# robot_board.net
KiCad netlist of a schematic drawn in EAGLE
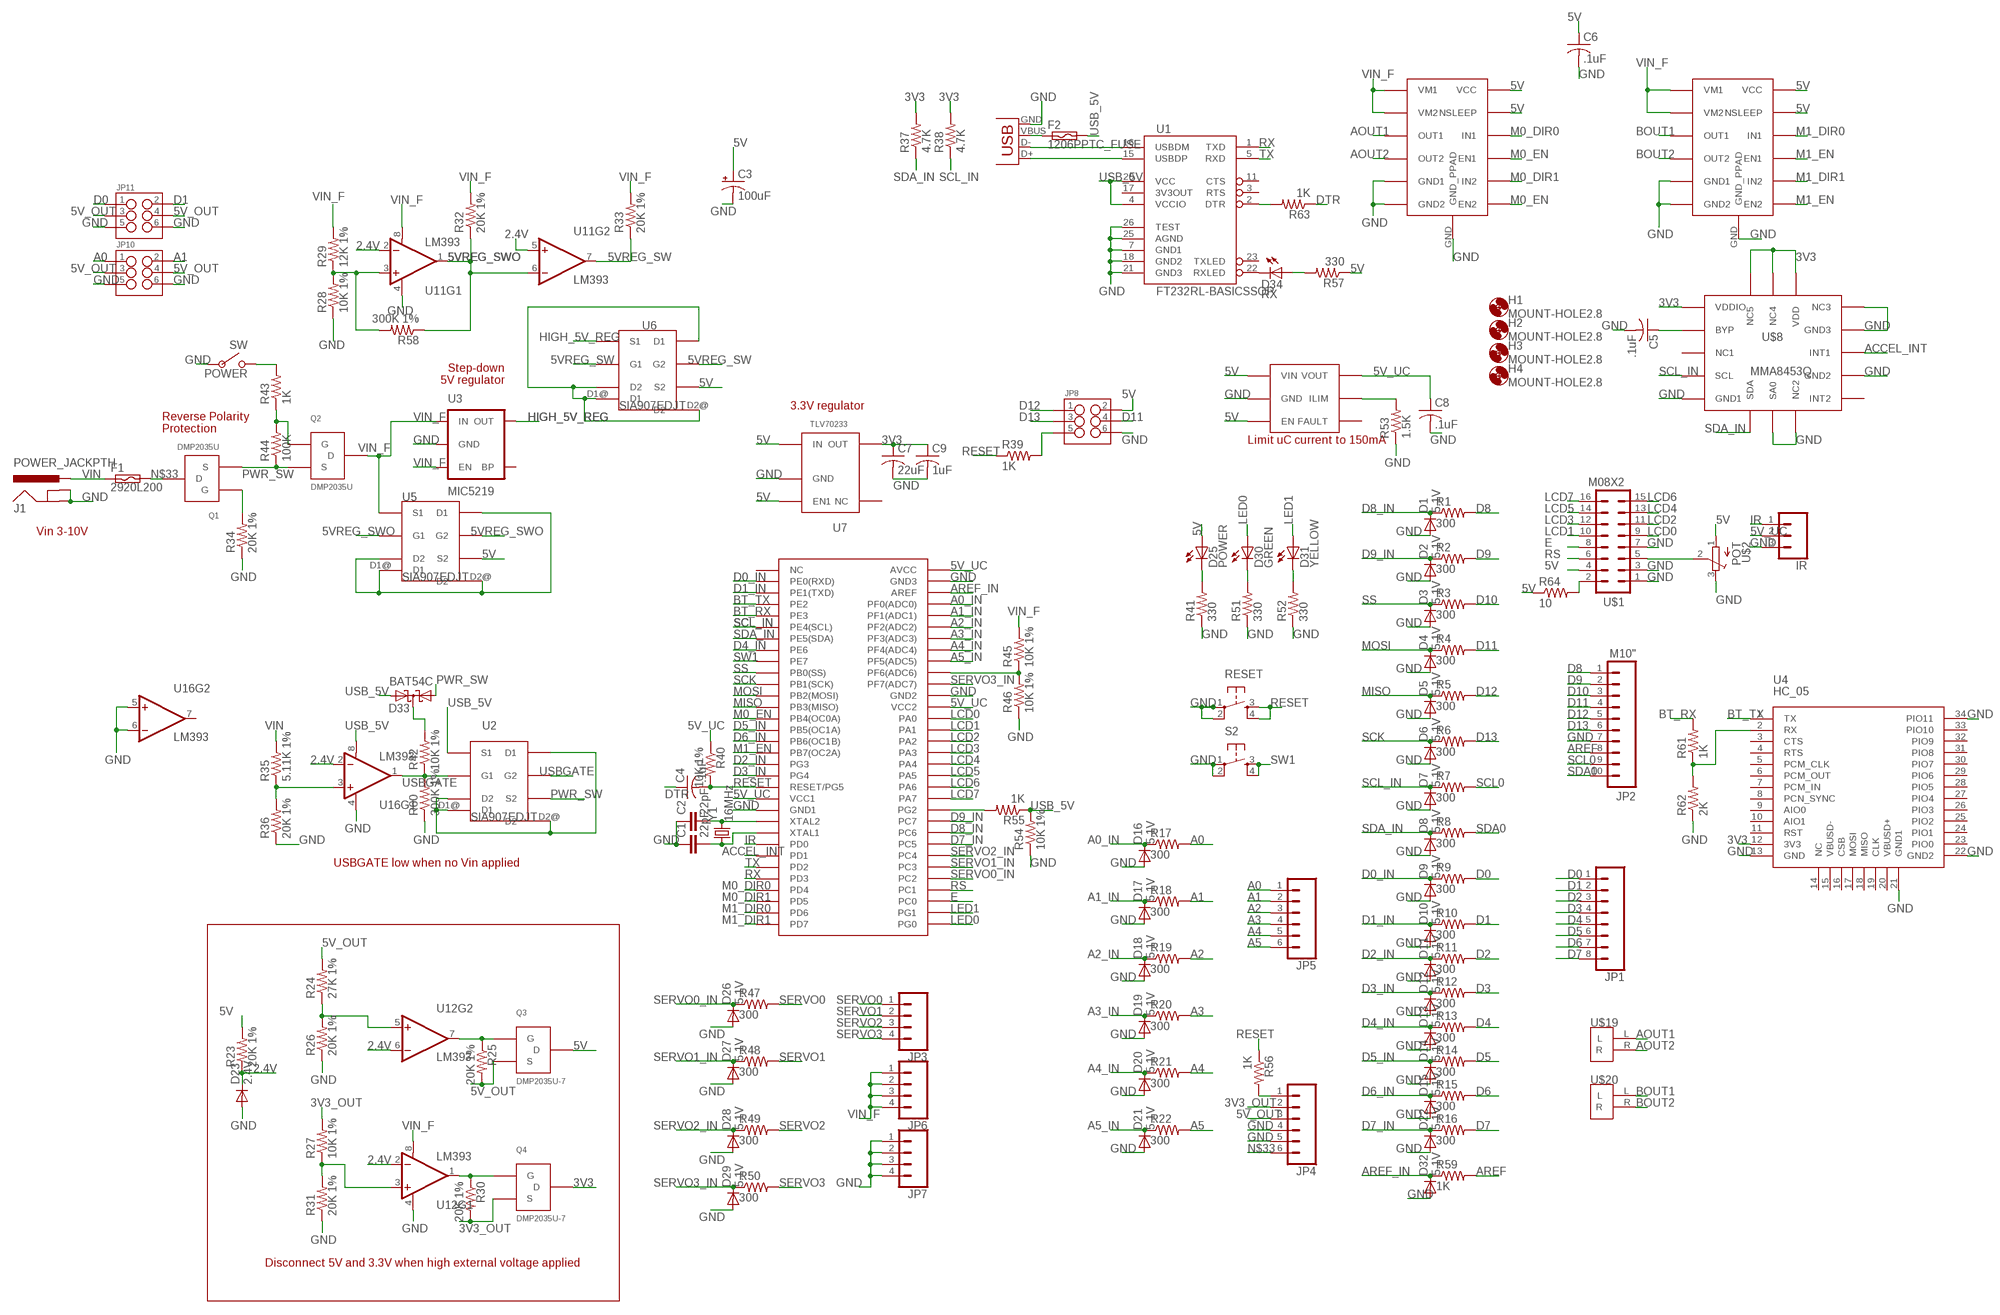
[diagram p0: schematic, sheet 1]

(export (version "E")
  (design (tool "Eeschema 10.0.6"))
  (components
    (comp (ref "C1")
      (value "22pF")
      (footprint "eagle-import:0805")
      (libsource (lib "eagle-import") (part "CAP0805"))
    )
    (comp (ref "C2")
      (value "22pF")
      (footprint "eagle-import:0805")
      (libsource (lib "eagle-import") (part "CAP0805"))
    )
    (comp (ref "C3")
      (value "100uF")
      (footprint "eagle-import:PANASONIC_D")
      (libsource (lib "eagle-import") (part "CAP_POLD"))
    )
    (comp (ref "C4")
      (value ".1uF")
      (footprint "eagle-import:C1206")
      (libsource (lib "eagle-import") (part "C-USC1206"))
    )
    (comp (ref "C5")
      (value ".1uF")
      (footprint "eagle-import:C1206")
      (libsource (lib "eagle-import") (part "C-USC1206"))
    )
    (comp (ref "C6")
      (value ".1uF")
      (footprint "eagle-import:C1206")
      (libsource (lib "eagle-import") (part "C-USC1206"))
    )
    (comp (ref "C7")
      (value "22uF")
      (footprint "eagle-import:C1206")
      (libsource (lib "eagle-import") (part "C-USC1206"))
    )
    (comp (ref "C8")
      (value ".1uF")
      (footprint "eagle-import:C1206")
      (libsource (lib "eagle-import") (part "C-USC1206"))
    )
    (comp (ref "C9")
      (value "1uF")
      (footprint "eagle-import:C1206")
      (libsource (lib "eagle-import") (part "C-USC1206"))
    )
    (comp (ref "D1")
      (value "5.1V")
      (footprint "eagle-import:SOT23-3")
      (libsource (lib "eagle-import") (part "DIODESOT23"))
    )
    (comp (ref "D2")
      (value "5.1V")
      (footprint "eagle-import:SOT23-3")
      (libsource (lib "eagle-import") (part "DIODESOT23"))
    )
    (comp (ref "D3")
      (value "5.1V")
      (footprint "eagle-import:SOT23-3")
      (libsource (lib "eagle-import") (part "DIODESOT23"))
    )
    (comp (ref "D4")
      (value "5.1V")
      (footprint "eagle-import:SOT23-3")
      (libsource (lib "eagle-import") (part "DIODESOT23"))
    )
    (comp (ref "D5")
      (value "5.1V")
      (footprint "eagle-import:SOT23-3")
      (libsource (lib "eagle-import") (part "DIODESOT23"))
    )
    (comp (ref "D6")
      (value "5.1V")
      (footprint "eagle-import:SOT23-3")
      (libsource (lib "eagle-import") (part "DIODESOT23"))
    )
    (comp (ref "D7")
      (value "5.1V")
      (footprint "eagle-import:SOT23-3")
      (libsource (lib "eagle-import") (part "DIODESOT23"))
    )
    (comp (ref "D8")
      (value "5.1V")
      (footprint "eagle-import:SOT23-3")
      (libsource (lib "eagle-import") (part "DIODESOT23"))
    )
    (comp (ref "D9")
      (value "5.1V")
      (footprint "eagle-import:SOT23-3")
      (libsource (lib "eagle-import") (part "DIODESOT23"))
    )
    (comp (ref "D10")
      (value "5.1V")
      (footprint "eagle-import:SOT23-3")
      (libsource (lib "eagle-import") (part "DIODESOT23"))
    )
    (comp (ref "D11")
      (value "5.1V")
      (footprint "eagle-import:SOT23-3")
      (libsource (lib "eagle-import") (part "DIODESOT23"))
    )
    (comp (ref "D12")
      (value "5.1V")
      (footprint "eagle-import:SOT23-3")
      (libsource (lib "eagle-import") (part "DIODESOT23"))
    )
    (comp (ref "D13")
      (value "5.1V")
      (footprint "eagle-import:SOT23-3")
      (libsource (lib "eagle-import") (part "DIODESOT23"))
    )
    (comp (ref "D14")
      (value "5.1V")
      (footprint "eagle-import:SOT23-3")
      (libsource (lib "eagle-import") (part "DIODESOT23"))
    )
    (comp (ref "D15")
      (value "5.1V")
      (footprint "eagle-import:SOT23-3")
      (libsource (lib "eagle-import") (part "DIODESOT23"))
    )
    (comp (ref "D16")
      (value "5.1V")
      (footprint "eagle-import:SOT23-3")
      (libsource (lib "eagle-import") (part "DIODESOT23"))
    )
    (comp (ref "D17")
      (value "5.1V")
      (footprint "eagle-import:SOT23-3")
      (libsource (lib "eagle-import") (part "DIODESOT23"))
    )
    (comp (ref "D18")
      (value "5.1V")
      (footprint "eagle-import:SOT23-3")
      (libsource (lib "eagle-import") (part "DIODESOT23"))
    )
    (comp (ref "D19")
      (value "5.1V")
      (footprint "eagle-import:SOT23-3")
      (libsource (lib "eagle-import") (part "DIODESOT23"))
    )
    (comp (ref "D20")
      (value "5.1V")
      (footprint "eagle-import:SOT23-3")
      (libsource (lib "eagle-import") (part "DIODESOT23"))
    )
    (comp (ref "D21")
      (value "5.1V")
      (footprint "eagle-import:SOT23-3")
      (libsource (lib "eagle-import") (part "DIODESOT23"))
    )
    (comp (ref "D22")
      (value "5.1V")
      (footprint "eagle-import:SOT23-3")
      (libsource (lib "eagle-import") (part "DIODESOT23"))
    )
    (comp (ref "D23")
      (value "2.4V")
      (footprint "eagle-import:SOT23-3")
      (libsource (lib "eagle-import") (part "DIODESOT23"))
    )
    (comp (ref "D25")
      (value "POWER")
      (footprint "eagle-import:LED-1206")
      (libsource (lib "eagle-import") (part "LED-GREENLILYPAD"))
    )
    (comp (ref "D26")
      (value "5.1V")
      (footprint "eagle-import:SOT23-3")
      (libsource (lib "eagle-import") (part "DIODESOT23"))
    )
    (comp (ref "D27")
      (value "5.1V")
      (footprint "eagle-import:SOT23-3")
      (libsource (lib "eagle-import") (part "DIODESOT23"))
    )
    (comp (ref "D28")
      (value "5.1V")
      (footprint "eagle-import:SOT23-3")
      (libsource (lib "eagle-import") (part "DIODESOT23"))
    )
    (comp (ref "D29")
      (value "5.1V")
      (footprint "eagle-import:SOT23-3")
      (libsource (lib "eagle-import") (part "DIODESOT23"))
    )
    (comp (ref "D30")
      (value "GREEN")
      (footprint "eagle-import:LED-1206")
      (libsource (lib "eagle-import") (part "LED-GREENLILYPAD"))
    )
    (comp (ref "D31")
      (value "YELLOW")
      (footprint "eagle-import:LED-1206")
      (libsource (lib "eagle-import") (part "LED-GREENLILYPAD"))
    )
    (comp (ref "D32")
      (value "5.1V")
      (footprint "eagle-import:SOT23-3")
      (libsource (lib "eagle-import") (part "DIODESOT23"))
    )
    (comp (ref "D33")
      (value "BAT54C")
      (footprint "eagle-import:SOT23")
      (libsource (lib "eagle-import") (part "BAT54C"))
    )
    (comp (ref "D34")
      (value "RX")
      (footprint "eagle-import:LED-1206")
      (libsource (lib "eagle-import") (part "LED-GREENLILYPAD"))
    )
    (comp (ref "F1")
      (value "2920L200")
      (footprint "eagle-import:SMD050F")
      (libsource (lib "eagle-import") (part "2920L200"))
    )
    (comp (ref "F2")
      (value "1206PPTC_FUSE")
      (footprint "eagle-import:R1206")
      (libsource (lib "eagle-import") (part "1206PPTC_FUSE"))
    )
    (comp (ref "H1")
      (value "MOUNT-HOLE2.8")
      (footprint "eagle-import:2,8")
      (libsource (lib "eagle-import") (part "MOUNT-HOLE2.8"))
    )
    (comp (ref "H2")
      (value "MOUNT-HOLE2.8")
      (footprint "eagle-import:2,8")
      (libsource (lib "eagle-import") (part "MOUNT-HOLE2.8"))
    )
    (comp (ref "H3")
      (value "MOUNT-HOLE2.8")
      (footprint "eagle-import:2,8")
      (libsource (lib "eagle-import") (part "MOUNT-HOLE2.8"))
    )
    (comp (ref "H4")
      (value "MOUNT-HOLE2.8")
      (footprint "eagle-import:2,8")
      (libsource (lib "eagle-import") (part "MOUNT-HOLE2.8"))
    )
    (comp (ref "IR")
      (value "M03PTH")
      (footprint "eagle-import:1X03")
      (libsource (lib "eagle-import") (part "M03PTH"))
    )
    (comp (ref "J1")
      (value "POWER_JACKPTH")
      (footprint "eagle-import:POWER_JACK_PTH")
      (libsource (lib "eagle-import") (part "POWER_JACKPTH"))
    )
    (comp (ref "JP1")
      (value "M081X08")
      (footprint "eagle-import:1X08")
      (libsource (lib "eagle-import") (part "M081X08"))
    )
    (comp (ref "JP2")
      (value "M10\"")
      (footprint "eagle-import:1X10")
      (libsource (lib "eagle-import") (part "M10{dblquote}"))
    )
    (comp (ref "JP3")
      (value "M04PTH")
      (footprint "eagle-import:1X04")
      (libsource (lib "eagle-import") (part "M04PTH"))
    )
    (comp (ref "JP4")
      (value "M06SIP")
      (footprint "eagle-import:1X06")
      (libsource (lib "eagle-import") (part "M06SIP"))
    )
    (comp (ref "JP5")
      (value "M06SIP")
      (footprint "eagle-import:1X06")
      (libsource (lib "eagle-import") (part "M06SIP"))
    )
    (comp (ref "JP6")
      (value "M04PTH")
      (footprint "eagle-import:1X04")
      (libsource (lib "eagle-import") (part "M04PTH"))
    )
    (comp (ref "JP7")
      (value "M04PTH")
      (footprint "eagle-import:1X04")
      (libsource (lib "eagle-import") (part "M04PTH"))
    )
    (comp (ref "JP8")
      (value "M03X22X3_SILK_SM")
      (footprint "eagle-import:2X3")
      (libsource (lib "eagle-import") (part "M03X22X3_SILK_SM"))
    )
    (comp (ref "JP9")
      (value "USB-B")
      (footprint "eagle-import:USB-B-PTH")
      (libsource (lib "eagle-import") (part "USBPTH"))
    )
    (comp (ref "JP10")
      (value "M03X22X3_SILK_SM")
      (footprint "eagle-import:2X3")
      (libsource (lib "eagle-import") (part "M03X22X3_SILK_SM"))
    )
    (comp (ref "JP11")
      (value "M03X22X3_SILK_SM")
      (footprint "eagle-import:2X3")
      (libsource (lib "eagle-import") (part "M03X22X3_SILK_SM"))
    )
    (comp (ref "POWER")
      (value "SW")
      (footprint "eagle-import:SW")
      (libsource (lib "eagle-import") (part "SW"))
    )
    (comp (ref "Q1")
      (value "DMP2035U")
      (footprint "eagle-import:SOT23")
      (libsource (lib "eagle-import") (part "DMP2035U"))
    )
    (comp (ref "Q2")
      (value "DMP2035U")
      (footprint "eagle-import:SOT23")
      (libsource (lib "eagle-import") (part "DMP2035U"))
    )
    (comp (ref "Q3")
      (value "DMP2035U-7")
      (footprint "eagle-import:SOT23@1")
      (libsource (lib "eagle-import") (part "DMP2035U-7"))
    )
    (comp (ref "Q4")
      (value "DMP2035U-7")
      (footprint "eagle-import:SOT23@1")
      (libsource (lib "eagle-import") (part "DMP2035U-7"))
    )
    (comp (ref "R1")
      (value "300")
      (footprint "eagle-import:R1206")
      (libsource (lib "eagle-import") (part "R-US_R1206"))
    )
    (comp (ref "R2")
      (value "300")
      (footprint "eagle-import:R1206")
      (libsource (lib "eagle-import") (part "R-US_R1206"))
    )
    (comp (ref "R3")
      (value "300")
      (footprint "eagle-import:R1206")
      (libsource (lib "eagle-import") (part "R-US_R1206"))
    )
    (comp (ref "R4")
      (value "300")
      (footprint "eagle-import:R1206")
      (libsource (lib "eagle-import") (part "R-US_R1206"))
    )
    (comp (ref "R5")
      (value "300")
      (footprint "eagle-import:R1206")
      (libsource (lib "eagle-import") (part "R-US_R1206"))
    )
    (comp (ref "R6")
      (value "300")
      (footprint "eagle-import:R1206")
      (libsource (lib "eagle-import") (part "R-US_R1206"))
    )
    (comp (ref "R7")
      (value "300")
      (footprint "eagle-import:R1206")
      (libsource (lib "eagle-import") (part "R-US_R1206"))
    )
    (comp (ref "R8")
      (value "300")
      (footprint "eagle-import:R1206")
      (libsource (lib "eagle-import") (part "R-US_R1206"))
    )
    (comp (ref "R9")
      (value "300")
      (footprint "eagle-import:R1206")
      (libsource (lib "eagle-import") (part "R-US_R1206"))
    )
    (comp (ref "R10")
      (value "300")
      (footprint "eagle-import:R1206")
      (libsource (lib "eagle-import") (part "R-US_R1206"))
    )
    (comp (ref "R11")
      (value "300")
      (footprint "eagle-import:R1206")
      (libsource (lib "eagle-import") (part "R-US_R1206"))
    )
    (comp (ref "R12")
      (value "300")
      (footprint "eagle-import:R1206")
      (libsource (lib "eagle-import") (part "R-US_R1206"))
    )
    (comp (ref "R13")
      (value "300")
      (footprint "eagle-import:R1206")
      (libsource (lib "eagle-import") (part "R-US_R1206"))
    )
    (comp (ref "R14")
      (value "300")
      (footprint "eagle-import:R1206")
      (libsource (lib "eagle-import") (part "R-US_R1206"))
    )
    (comp (ref "R15")
      (value "300")
      (footprint "eagle-import:R1206")
      (libsource (lib "eagle-import") (part "R-US_R1206"))
    )
    (comp (ref "R16")
      (value "300")
      (footprint "eagle-import:R1206")
      (libsource (lib "eagle-import") (part "R-US_R1206"))
    )
    (comp (ref "R17")
      (value "300")
      (footprint "eagle-import:R1206")
      (libsource (lib "eagle-import") (part "R-US_R1206"))
    )
    (comp (ref "R18")
      (value "300")
      (footprint "eagle-import:R1206")
      (libsource (lib "eagle-import") (part "R-US_R1206"))
    )
    (comp (ref "R19")
      (value "300")
      (footprint "eagle-import:R1206")
      (libsource (lib "eagle-import") (part "R-US_R1206"))
    )
    (comp (ref "R20")
      (value "300")
      (footprint "eagle-import:R1206")
      (libsource (lib "eagle-import") (part "R-US_R1206"))
    )
    (comp (ref "R21")
      (value "300")
      (footprint "eagle-import:R1206")
      (libsource (lib "eagle-import") (part "R-US_R1206"))
    )
    (comp (ref "R22")
      (value "300")
      (footprint "eagle-import:R1206")
      (libsource (lib "eagle-import") (part "R-US_R1206"))
    )
    (comp (ref "R23")
      (value "20K 1%")
      (footprint "eagle-import:R1206")
      (libsource (lib "eagle-import") (part "R-US_R1206"))
    )
    (comp (ref "R24")
      (value "27K 1%")
      (footprint "eagle-import:R1206")
      (libsource (lib "eagle-import") (part "R-US_R1206"))
    )
    (comp (ref "R25")
      (value "20K 1%")
      (footprint "eagle-import:R1206")
      (libsource (lib "eagle-import") (part "R-US_R1206"))
    )
    (comp (ref "R26")
      (value "20K 1%")
      (footprint "eagle-import:R1206")
      (libsource (lib "eagle-import") (part "R-US_R1206"))
    )
    (comp (ref "R27")
      (value "10K 1%")
      (footprint "eagle-import:R1206")
      (libsource (lib "eagle-import") (part "R-US_R1206"))
    )
    (comp (ref "R28")
      (value "10K 1%")
      (footprint "eagle-import:R1206")
      (libsource (lib "eagle-import") (part "R-US_R1206"))
    )
    (comp (ref "R29")
      (value "12K 1%")
      (footprint "eagle-import:R1206")
      (libsource (lib "eagle-import") (part "R-US_R1206"))
    )
    (comp (ref "R30")
      (value "20K 1%")
      (footprint "eagle-import:R1206")
      (libsource (lib "eagle-import") (part "R-US_R1206"))
    )
    (comp (ref "R31")
      (value "20K 1%")
      (footprint "eagle-import:R1206")
      (libsource (lib "eagle-import") (part "R-US_R1206"))
    )
    (comp (ref "R32")
      (value "20K 1%")
      (footprint "eagle-import:R1206")
      (libsource (lib "eagle-import") (part "R-US_R1206"))
    )
    (comp (ref "R33")
      (value "20K 1%")
      (footprint "eagle-import:R1206")
      (libsource (lib "eagle-import") (part "R-US_R1206"))
    )
    (comp (ref "R34")
      (value "20K 1%")
      (footprint "eagle-import:R1206")
      (libsource (lib "eagle-import") (part "R-US_R1206"))
    )
    (comp (ref "R35")
      (value "5.11K 1%")
      (footprint "eagle-import:R1206")
      (libsource (lib "eagle-import") (part "R-US_R1206"))
    )
    (comp (ref "R36")
      (value "20K 1%")
      (footprint "eagle-import:R1206")
      (libsource (lib "eagle-import") (part "R-US_R1206"))
    )
    (comp (ref "R37")
      (value "4.7K")
      (footprint "eagle-import:R1206")
      (libsource (lib "eagle-import") (part "R-US_R1206"))
    )
    (comp (ref "R38")
      (value "4.7K")
      (footprint "eagle-import:R1206")
      (libsource (lib "eagle-import") (part "R-US_R1206"))
    )
    (comp (ref "R39")
      (value "1K")
      (footprint "eagle-import:R1206")
      (libsource (lib "eagle-import") (part "R-US_R1206"))
    )
    (comp (ref "R40")
      (value "10K 1%")
      (footprint "eagle-import:R1206")
      (libsource (lib "eagle-import") (part "R-US_R1206"))
    )
    (comp (ref "R41")
      (value "330")
      (footprint "eagle-import:R1206")
      (libsource (lib "eagle-import") (part "R-US_R1206"))
    )
    (comp (ref "R42")
      (value "10K 1%")
      (footprint "eagle-import:R1206")
      (libsource (lib "eagle-import") (part "R-US_R1206"))
    )
    (comp (ref "R43")
      (value "1K")
      (footprint "eagle-import:R1206")
      (libsource (lib "eagle-import") (part "R-US_R1206"))
    )
    (comp (ref "R44")
      (value "100K")
      (footprint "eagle-import:R1206")
      (libsource (lib "eagle-import") (part "R-US_R1206"))
    )
    (comp (ref "R45")
      (value "10K 1%")
      (footprint "eagle-import:R1206")
      (libsource (lib "eagle-import") (part "R-US_R1206"))
    )
    (comp (ref "R46")
      (value "10K 1%")
      (footprint "eagle-import:R1206")
      (libsource (lib "eagle-import") (part "R-US_R1206"))
    )
    (comp (ref "R47")
      (value "300")
      (footprint "eagle-import:R1206")
      (libsource (lib "eagle-import") (part "R-US_R1206"))
    )
    (comp (ref "R48")
      (value "300")
      (footprint "eagle-import:R1206")
      (libsource (lib "eagle-import") (part "R-US_R1206"))
    )
    (comp (ref "R49")
      (value "300")
      (footprint "eagle-import:R1206")
      (libsource (lib "eagle-import") (part "R-US_R1206"))
    )
    (comp (ref "R50")
      (value "300")
      (footprint "eagle-import:R1206")
      (libsource (lib "eagle-import") (part "R-US_R1206"))
    )
    (comp (ref "R51")
      (value "330")
      (footprint "eagle-import:R1206")
      (libsource (lib "eagle-import") (part "R-US_R1206"))
    )
    (comp (ref "R52")
      (value "330")
      (footprint "eagle-import:R1206")
      (libsource (lib "eagle-import") (part "R-US_R1206"))
    )
    (comp (ref "R53")
      (value "1.5K")
      (footprint "eagle-import:R1206")
      (libsource (lib "eagle-import") (part "R-US_R1206"))
    )
    (comp (ref "R54")
      (value "10K 1%")
      (footprint "eagle-import:R1206")
      (libsource (lib "eagle-import") (part "R-US_R1206"))
    )
    (comp (ref "R55")
      (value "1K")
      (footprint "eagle-import:R1206")
      (libsource (lib "eagle-import") (part "R-US_R1206"))
    )
    (comp (ref "R56")
      (value "1K")
      (footprint "eagle-import:R1206")
      (libsource (lib "eagle-import") (part "R-US_R1206"))
    )
    (comp (ref "R57")
      (value "330")
      (footprint "eagle-import:R1206")
      (libsource (lib "eagle-import") (part "R-US_R1206"))
    )
    (comp (ref "R58")
      (value "300K 1%")
      (footprint "eagle-import:R1206")
      (libsource (lib "eagle-import") (part "R-US_R1206"))
    )
    (comp (ref "R59")
      (value "1K")
      (footprint "eagle-import:R1206")
      (libsource (lib "eagle-import") (part "R-US_R1206"))
    )
    (comp (ref "R60")
      (value "300K 1%")
      (footprint "eagle-import:R1206")
      (libsource (lib "eagle-import") (part "R-US_R1206"))
    )
    (comp (ref "R61")
      (value "1K")
      (footprint "eagle-import:R1206")
      (libsource (lib "eagle-import") (part "R-US_R1206"))
    )
    (comp (ref "R62")
      (value "2K")
      (footprint "eagle-import:R1206")
      (libsource (lib "eagle-import") (part "R-US_R1206"))
    )
    (comp (ref "R63")
      (value "1K")
      (footprint "eagle-import:R1206")
      (libsource (lib "eagle-import") (part "R-US_R1206"))
    )
    (comp (ref "R64")
      (value "10")
      (footprint "eagle-import:R1206")
      (libsource (lib "eagle-import") (part "R-US_R1206"))
    )
    (comp (ref "RESET")
      (value "TAC_SWITCHPTH")
      (footprint "eagle-import:TACTILE-PTH")
      (libsource (lib "eagle-import") (part "TAC_SWITCHPTH"))
    )
    (comp (ref "S2")
      (value "TAC_SWITCHPTH")
      (footprint "eagle-import:TACTILE-PTH")
      (libsource (lib "eagle-import") (part "TAC_SWITCHPTH"))
    )
    (comp (ref "U$1")
      (value "M08X2")
      (footprint "eagle-import:2X8")
      (libsource (lib "eagle-import") (part "M08X2"))
    )
    (comp (ref "U$2")
      (value "POT")
      (footprint "eagle-import:POT")
      (libsource (lib "eagle-import") (part "POT"))
    )
    (comp (ref "U$8")
      (value "MMA8453Q")
      (footprint "eagle-import:QFN-COL")
      (libsource (lib "eagle-import") (part "MMA8453Q"))
    )
    (comp (ref "U$19")
      (value "2POS_TERMINAL")
      (footprint "eagle-import:2POS_TERMINAL")
      (libsource (lib "eagle-import") (part "2POS_TERMINAL"))
    )
    (comp (ref "U$20")
      (value "2POS_TERMINAL")
      (footprint "eagle-import:2POS_TERMINAL")
      (libsource (lib "eagle-import") (part "2POS_TERMINAL"))
    )
    (comp (ref "U1")
      (value "FT232RL-BASICSSOP")
      (footprint "eagle-import:SSOP28DB")
      (libsource (lib "eagle-import") (part "FT232RL-BASICSSOP"))
    )
    (comp (ref "U2")
      (value "SIA907EDJT")
      (footprint "eagle-import:SC70T")
      (libsource (lib "eagle-import") (part "SIA907EDJT"))
    )
    (comp (ref "U3")
      (value "MIC5219")
      (footprint "eagle-import:SOT23-5")
      (libsource (lib "eagle-import") (part "MIC52055V"))
    )
    (comp (ref "U4")
      (value "HC_05")
      (footprint "eagle-import:BLUETOOTH_SMD")
      (libsource (lib "eagle-import") (part "HC_05"))
    )
    (comp (ref "U5")
      (value "SIA907EDJT")
      (footprint "eagle-import:SC70T")
      (libsource (lib "eagle-import") (part "SIA907EDJT"))
    )
    (comp (ref "U6")
      (value "SIA907EDJT")
      (footprint "eagle-import:SC70T")
      (libsource (lib "eagle-import") (part "SIA907EDJT"))
    )
    (comp (ref "U7")
      (value "TLV70233")
      (footprint "eagle-import:SOT-23-5")
      (libsource (lib "eagle-import") (part "TLV70233"))
    )
    (comp (ref "U8")
      (value "MIC2009A")
      (footprint "eagle-import:SOT23-M5")
      (libsource (lib "eagle-import") (part "MIC2009A"))
    )
    (comp (ref "U9")
      (value "DRV8839")
      (footprint "eagle-import:PWSON-N12")
      (libsource (lib "eagle-import") (part "DRV8839"))
    )
    (comp (ref "U10")
      (value "DRV8839")
      (footprint "eagle-import:PWSON-N12")
      (libsource (lib "eagle-import") (part "DRV8839"))
    )
    (comp (ref "U11")
      (value "LM393")
      (footprint "eagle-import:SO08")
      (libsource (lib "eagle-import") (part "LM393"))
    )
    (comp (ref "U12")
      (value "LM393")
      (footprint "eagle-import:SO08")
      (libsource (lib "eagle-import") (part "LM393"))
    )
    (comp (ref "U16")
      (value "LM393")
      (footprint "eagle-import:SO08")
      (libsource (lib "eagle-import") (part "LM393"))
    )
    (comp (ref "U17")
      (value "ATMEGA325PA")
      (footprint "eagle-import:TQFP64")
      (libsource (lib "eagle-import") (part "ATMEGA325PA"))
    )
    (comp (ref "Y1")
      (value "16MHz")
      (footprint "eagle-import:CRYSTAL-SMD-10.5X4.8-2PIN")
      (libsource (lib "eagle-import") (part "CRYSTAL10.5X4.8"))
    )
  )
  (nets
    (net (code "1") (name "/2.4V") (class "Default")
      (node (ref "D23") (pin "3") (pinfunction "C_3") (pintype "passive"))
      (node (ref "R23") (pin "1") (pinfunction "1_1") (pintype "passive"))
      (node (ref "U11") (pin "2") (pinfunction "-IN_2") (pintype "input"))
      (node (ref "U11") (pin "5") (pinfunction "+IN_5") (pintype "input"))
      (node (ref "U12") (pin "2") (pinfunction "-IN_2") (pintype "input"))
      (node (ref "U12") (pin "6") (pinfunction "-IN_6") (pintype "input"))
      (node (ref "U16") (pin "2") (pinfunction "-IN_2") (pintype "input"))
    )
    (net (code "2") (name "/3V3") (class "Default")
      (node (ref "C7") (pin "1") (pinfunction "1_1") (pintype "passive"))
      (node (ref "C9") (pin "1") (pinfunction "1_1") (pintype "passive"))
      (node (ref "Q4") (pin "3") (pinfunction "D_3") (pintype "bidirectional"))
      (node (ref "R37") (pin "2") (pinfunction "2_2") (pintype "passive"))
      (node (ref "R38") (pin "2") (pinfunction "2_2") (pintype "passive"))
      (node (ref "U$8") (pin "P$1") (pinfunction "VDDIO_P$1") (pintype "bidirectional"))
      (node (ref "U$8") (pin "P$14") (pinfunction "VDD_P$14") (pintype "bidirectional"))
      (node (ref "U$8") (pin "P$15") (pinfunction "NC4_P$15") (pintype "bidirectional"))
      (node (ref "U$8") (pin "P$16") (pinfunction "NC5_P$16") (pintype "bidirectional"))
      (node (ref "U4") (pin "12") (pinfunction "3V3_12") (pintype "bidirectional"))
      (node (ref "U7") (pin "P$4") (pinfunction "OUT_P$4") (pintype "bidirectional"))
    )
    (net (code "3") (name "/3V3_OUT") (class "Default")
      (node (ref "JP4") (pin "2") (pinfunction "2_2") (pintype "passive"))
      (node (ref "Q4") (pin "2") (pinfunction "S_2") (pintype "bidirectional"))
      (node (ref "R27") (pin "2") (pinfunction "2_2") (pintype "passive"))
      (node (ref "R30") (pin "2") (pinfunction "2_2") (pintype "passive"))
    )
    (net (code "4") (name "/5V") (class "Default")
      (node (ref "C3") (pin "+") (pinfunction "+_+") (pintype "passive"))
      (node (ref "C6") (pin "1") (pinfunction "1_1") (pintype "passive"))
      (node (ref "D25") (pin "A") (pinfunction "A_A") (pintype "passive"))
      (node (ref "JP8") (pin "2") (pinfunction "2_2") (pintype "bidirectional"))
      (node (ref "Q3") (pin "3") (pinfunction "D_3") (pintype "bidirectional"))
      (node (ref "R23") (pin "2") (pinfunction "2_2") (pintype "passive"))
      (node (ref "R57") (pin "1") (pinfunction "1_1") (pintype "passive"))
      (node (ref "R64") (pin "1") (pinfunction "1_1") (pintype "passive"))
      (node (ref "U$1") (pin "4") (pinfunction "4_4") (pintype "passive"))
      (node (ref "U$2") (pin "1") (pinfunction "A_1") (pintype "passive"))
      (node (ref "U10") (pin "P$7") (pinfunction "VCC_P$7") (pintype "bidirectional"))
      (node (ref "U10") (pin "P$8") (pinfunction "NSLEEP_P$8") (pintype "bidirectional"))
      (node (ref "U5") (pin "S2") (pinfunction "S2_S2") (pintype "bidirectional"))
      (node (ref "U6") (pin "S2") (pinfunction "S2_S2") (pintype "bidirectional"))
      (node (ref "U7") (pin "P$1") (pinfunction "IN_P$1") (pintype "bidirectional"))
      (node (ref "U7") (pin "P$3") (pinfunction "EN1_P$3") (pintype "bidirectional"))
      (node (ref "U8") (pin "P$1") (pinfunction "VIN_P$1") (pintype "bidirectional"))
      (node (ref "U8") (pin "P$3") (pinfunction "EN_P$3") (pintype "bidirectional"))
      (node (ref "U9") (pin "P$7") (pinfunction "VCC_P$7") (pintype "bidirectional"))
      (node (ref "U9") (pin "P$8") (pinfunction "NSLEEP_P$8") (pintype "bidirectional"))
    )
    (net (code "5") (name "/5VREG_SW") (class "Default")
      (node (ref "R33") (pin "1") (pinfunction "1_1") (pintype "passive"))
      (node (ref "U11") (pin "7") (pinfunction "OUT_7") (pintype "output"))
      (node (ref "U6") (pin "G1") (pinfunction "G1_G1") (pintype "bidirectional"))
      (node (ref "U6") (pin "G2") (pinfunction "G2_G2") (pintype "bidirectional"))
    )
    (net (code "6") (name "/5VREG_SWO") (class "Default")
      (node (ref "R32") (pin "1") (pinfunction "1_1") (pintype "passive"))
      (node (ref "R58") (pin "1") (pinfunction "1_1") (pintype "passive"))
      (node (ref "U11") (pin "1") (pinfunction "OUT_1") (pintype "output"))
      (node (ref "U11") (pin "6") (pinfunction "-IN_6") (pintype "input"))
      (node (ref "U5") (pin "G1") (pinfunction "G1_G1") (pintype "bidirectional"))
      (node (ref "U5") (pin "G2") (pinfunction "G2_G2") (pintype "bidirectional"))
    )
    (net (code "7") (name "/5V_OUT") (class "Default")
      (node (ref "JP10") (pin "3") (pinfunction "3_3") (pintype "bidirectional"))
      (node (ref "JP10") (pin "4") (pinfunction "4_4") (pintype "bidirectional"))
      (node (ref "JP11") (pin "3") (pinfunction "3_3") (pintype "bidirectional"))
      (node (ref "JP11") (pin "4") (pinfunction "4_4") (pintype "bidirectional"))
      (node (ref "JP4") (pin "3") (pinfunction "3_3") (pintype "passive"))
      (node (ref "Q3") (pin "2") (pinfunction "S_2") (pintype "bidirectional"))
      (node (ref "R24") (pin "2") (pinfunction "2_2") (pintype "passive"))
      (node (ref "R25") (pin "2") (pinfunction "2_2") (pintype "passive"))
    )
    (net (code "8") (name "/5V_UC") (class "Default")
      (node (ref "C8") (pin "1") (pinfunction "1_1") (pintype "passive"))
      (node (ref "IR") (pin "2") (pinfunction "2_2") (pintype "passive"))
      (node (ref "R40") (pin "1") (pinfunction "1_1") (pintype "passive"))
      (node (ref "U17") (pin "21") (pinfunction "VCC1_21") (pintype "bidirectional"))
      (node (ref "U17") (pin "52") (pinfunction "VCC2_52") (pintype "bidirectional"))
      (node (ref "U17") (pin "64") (pinfunction "AVCC_64") (pintype "bidirectional"))
      (node (ref "U8") (pin "P$6") (pinfunction "VOUT_P$6") (pintype "bidirectional"))
    )
    (net (code "9") (name "/A0") (class "Default")
      (node (ref "JP10") (pin "1") (pinfunction "1_1") (pintype "bidirectional"))
      (node (ref "JP5") (pin "1") (pinfunction "1_1") (pintype "passive"))
      (node (ref "R17") (pin "2") (pinfunction "2_2") (pintype "passive"))
    )
    (net (code "10") (name "/A0_IN") (class "Default")
      (node (ref "D16") (pin "3") (pinfunction "C_3") (pintype "passive"))
      (node (ref "R17") (pin "1") (pinfunction "1_1") (pintype "passive"))
      (node (ref "U17") (pin "61") (pinfunction "PF0(ADC0)_61") (pintype "bidirectional"))
    )
    (net (code "11") (name "/A1") (class "Default")
      (node (ref "JP10") (pin "2") (pinfunction "2_2") (pintype "bidirectional"))
      (node (ref "JP5") (pin "2") (pinfunction "2_2") (pintype "passive"))
      (node (ref "R18") (pin "2") (pinfunction "2_2") (pintype "passive"))
    )
    (net (code "12") (name "/A1_IN") (class "Default")
      (node (ref "D17") (pin "3") (pinfunction "C_3") (pintype "passive"))
      (node (ref "R18") (pin "1") (pinfunction "1_1") (pintype "passive"))
      (node (ref "U17") (pin "60") (pinfunction "PF1(ADC1)_60") (pintype "bidirectional"))
    )
    (net (code "13") (name "/A2") (class "Default")
      (node (ref "JP5") (pin "3") (pinfunction "3_3") (pintype "passive"))
      (node (ref "R19") (pin "2") (pinfunction "2_2") (pintype "passive"))
    )
    (net (code "14") (name "/A2_IN") (class "Default")
      (node (ref "D18") (pin "3") (pinfunction "C_3") (pintype "passive"))
      (node (ref "R19") (pin "1") (pinfunction "1_1") (pintype "passive"))
      (node (ref "U17") (pin "59") (pinfunction "PF2(ADC2)_59") (pintype "bidirectional"))
    )
    (net (code "15") (name "/A3") (class "Default")
      (node (ref "JP5") (pin "4") (pinfunction "4_4") (pintype "passive"))
      (node (ref "R20") (pin "2") (pinfunction "2_2") (pintype "passive"))
    )
    (net (code "16") (name "/A3_IN") (class "Default")
      (node (ref "D19") (pin "3") (pinfunction "C_3") (pintype "passive"))
      (node (ref "R20") (pin "1") (pinfunction "1_1") (pintype "passive"))
      (node (ref "U17") (pin "58") (pinfunction "PF3(ADC3)_58") (pintype "bidirectional"))
    )
    (net (code "17") (name "/A4") (class "Default")
      (node (ref "JP5") (pin "5") (pinfunction "5_5") (pintype "passive"))
      (node (ref "R21") (pin "2") (pinfunction "2_2") (pintype "passive"))
    )
    (net (code "18") (name "/A4_IN") (class "Default")
      (node (ref "D20") (pin "3") (pinfunction "C_3") (pintype "passive"))
      (node (ref "R21") (pin "1") (pinfunction "1_1") (pintype "passive"))
      (node (ref "U17") (pin "57") (pinfunction "PF4(ADC4)_57") (pintype "bidirectional"))
    )
    (net (code "19") (name "/A5") (class "Default")
      (node (ref "JP5") (pin "6") (pinfunction "6_6") (pintype "passive"))
      (node (ref "R22") (pin "2") (pinfunction "2_2") (pintype "passive"))
    )
    (net (code "20") (name "/A5_IN") (class "Default")
      (node (ref "D21") (pin "3") (pinfunction "C_3") (pintype "passive"))
      (node (ref "R22") (pin "1") (pinfunction "1_1") (pintype "passive"))
      (node (ref "U17") (pin "56") (pinfunction "PF5(ADC5)_56") (pintype "bidirectional"))
    )
    (net (code "21") (name "/ACCEL_INT") (class "Default")
      (node (ref "U$8") (pin "P$11") (pinfunction "INT1_P$11") (pintype "bidirectional"))
      (node (ref "U17") (pin "26") (pinfunction "PD1_26") (pintype "bidirectional"))
    )
    (net (code "22") (name "/AOUT1") (class "Default")
      (node (ref "U$19") (pin "L") (pinfunction "L_L") (pintype "bidirectional"))
      (node (ref "U9") (pin "P$3") (pinfunction "OUT1_P$3") (pintype "bidirectional"))
    )
    (net (code "23") (name "/AOUT2") (class "Default")
      (node (ref "U$19") (pin "R") (pinfunction "R_R") (pintype "bidirectional"))
      (node (ref "U9") (pin "P$4") (pinfunction "OUT2_P$4") (pintype "bidirectional"))
    )
    (net (code "24") (name "/AREF") (class "Default")
      (node (ref "JP2") (pin "8") (pinfunction "8_8") (pintype "passive"))
      (node (ref "R59") (pin "2") (pinfunction "2_2") (pintype "passive"))
    )
    (net (code "25") (name "/AREF_IN") (class "Default")
      (node (ref "D32") (pin "3") (pinfunction "C_3") (pintype "passive"))
      (node (ref "R59") (pin "1") (pinfunction "1_1") (pintype "passive"))
      (node (ref "U17") (pin "62") (pinfunction "AREF_62") (pintype "bidirectional"))
    )
    (net (code "26") (name "/BOUT1") (class "Default")
      (node (ref "U$20") (pin "L") (pinfunction "L_L") (pintype "bidirectional"))
      (node (ref "U10") (pin "P$3") (pinfunction "OUT1_P$3") (pintype "bidirectional"))
    )
    (net (code "27") (name "/BOUT2") (class "Default")
      (node (ref "U$20") (pin "R") (pinfunction "R_R") (pintype "bidirectional"))
      (node (ref "U10") (pin "P$4") (pinfunction "OUT2_P$4") (pintype "bidirectional"))
    )
    (net (code "28") (name "/BT_RX") (class "Default")
      (node (ref "R61") (pin "2") (pinfunction "2_2") (pintype "passive"))
      (node (ref "U17") (pin "5") (pinfunction "PE3_5") (pintype "bidirectional"))
    )
    (net (code "29") (name "/BT_TX") (class "Default")
      (node (ref "U17") (pin "4") (pinfunction "PE2_4") (pintype "bidirectional"))
      (node (ref "U4") (pin "1") (pinfunction "TX_1") (pintype "bidirectional"))
    )
    (net (code "30") (name "/D0") (class "Default")
      (node (ref "JP1") (pin "1") (pinfunction "1_1") (pintype "passive"))
      (node (ref "JP11") (pin "1") (pinfunction "1_1") (pintype "bidirectional"))
      (node (ref "R9") (pin "2") (pinfunction "2_2") (pintype "passive"))
    )
    (net (code "31") (name "/D0_IN") (class "Default")
      (node (ref "D9") (pin "3") (pinfunction "C_3") (pintype "passive"))
      (node (ref "R9") (pin "1") (pinfunction "1_1") (pintype "passive"))
      (node (ref "U17") (pin "2") (pinfunction "PE0(RXD)_2") (pintype "bidirectional"))
    )
    (net (code "32") (name "/D1") (class "Default")
      (node (ref "JP1") (pin "2") (pinfunction "2_2") (pintype "passive"))
      (node (ref "JP11") (pin "2") (pinfunction "2_2") (pintype "bidirectional"))
      (node (ref "R10") (pin "2") (pinfunction "2_2") (pintype "passive"))
    )
    (net (code "33") (name "/D1_IN") (class "Default")
      (node (ref "D10") (pin "3") (pinfunction "C_3") (pintype "passive"))
      (node (ref "R10") (pin "1") (pinfunction "1_1") (pintype "passive"))
      (node (ref "U17") (pin "3") (pinfunction "PE1(TXD)_3") (pintype "bidirectional"))
    )
    (net (code "34") (name "/D2") (class "Default")
      (node (ref "JP1") (pin "3") (pinfunction "3_3") (pintype "passive"))
      (node (ref "R11") (pin "2") (pinfunction "2_2") (pintype "passive"))
    )
    (net (code "35") (name "/D2_IN") (class "Default")
      (node (ref "D11") (pin "3") (pinfunction "C_3") (pintype "passive"))
      (node (ref "R11") (pin "1") (pinfunction "1_1") (pintype "passive"))
      (node (ref "U17") (pin "18") (pinfunction "PG3_18") (pintype "bidirectional"))
    )
    (net (code "36") (name "/D3") (class "Default")
      (node (ref "JP1") (pin "4") (pinfunction "4_4") (pintype "passive"))
      (node (ref "R12") (pin "2") (pinfunction "2_2") (pintype "passive"))
    )
    (net (code "37") (name "/D3_IN") (class "Default")
      (node (ref "D12") (pin "3") (pinfunction "C_3") (pintype "passive"))
      (node (ref "R12") (pin "1") (pinfunction "1_1") (pintype "passive"))
      (node (ref "U17") (pin "19") (pinfunction "PG4_19") (pintype "bidirectional"))
    )
    (net (code "38") (name "/D4") (class "Default")
      (node (ref "JP1") (pin "5") (pinfunction "5_5") (pintype "passive"))
      (node (ref "R13") (pin "2") (pinfunction "2_2") (pintype "passive"))
    )
    (net (code "39") (name "/D4_IN") (class "Default")
      (node (ref "D13") (pin "3") (pinfunction "C_3") (pintype "passive"))
      (node (ref "R13") (pin "1") (pinfunction "1_1") (pintype "passive"))
      (node (ref "U17") (pin "8") (pinfunction "PE6_8") (pintype "bidirectional"))
    )
    (net (code "40") (name "/D5") (class "Default")
      (node (ref "JP1") (pin "6") (pinfunction "6_6") (pintype "passive"))
      (node (ref "R14") (pin "2") (pinfunction "2_2") (pintype "passive"))
    )
    (net (code "41") (name "/D5_IN") (class "Default")
      (node (ref "D14") (pin "3") (pinfunction "C_3") (pintype "passive"))
      (node (ref "R14") (pin "1") (pinfunction "1_1") (pintype "passive"))
      (node (ref "U17") (pin "15") (pinfunction "PB5(OC1A)_15") (pintype "bidirectional"))
    )
    (net (code "42") (name "/D6") (class "Default")
      (node (ref "JP1") (pin "7") (pinfunction "7_7") (pintype "passive"))
      (node (ref "R15") (pin "2") (pinfunction "2_2") (pintype "passive"))
    )
    (net (code "43") (name "/D6_IN") (class "Default")
      (node (ref "D15") (pin "3") (pinfunction "C_3") (pintype "passive"))
      (node (ref "R15") (pin "1") (pinfunction "1_1") (pintype "passive"))
      (node (ref "U17") (pin "16") (pinfunction "PB6(OC1B)_16") (pintype "bidirectional"))
    )
    (net (code "44") (name "/D7") (class "Default")
      (node (ref "JP1") (pin "8") (pinfunction "8_8") (pintype "passive"))
      (node (ref "R16") (pin "2") (pinfunction "2_2") (pintype "passive"))
    )
    (net (code "45") (name "/D7_IN") (class "Default")
      (node (ref "D22") (pin "3") (pinfunction "C_3") (pintype "passive"))
      (node (ref "R16") (pin "1") (pinfunction "1_1") (pintype "passive"))
      (node (ref "U17") (pin "40") (pinfunction "PC5_40") (pintype "bidirectional"))
    )
    (net (code "46") (name "/D8") (class "Default")
      (node (ref "JP2") (pin "1") (pinfunction "1_1") (pintype "passive"))
      (node (ref "R1") (pin "2") (pinfunction "2_2") (pintype "passive"))
    )
    (net (code "47") (name "/D8_IN") (class "Default")
      (node (ref "D1") (pin "3") (pinfunction "C_3") (pintype "passive"))
      (node (ref "R1") (pin "1") (pinfunction "1_1") (pintype "passive"))
      (node (ref "U17") (pin "41") (pinfunction "PC6_41") (pintype "bidirectional"))
    )
    (net (code "48") (name "/D9") (class "Default")
      (node (ref "JP2") (pin "2") (pinfunction "2_2") (pintype "passive"))
      (node (ref "R2") (pin "2") (pinfunction "2_2") (pintype "passive"))
    )
    (net (code "49") (name "/D9_IN") (class "Default")
      (node (ref "D2") (pin "3") (pinfunction "C_3") (pintype "passive"))
      (node (ref "R2") (pin "1") (pinfunction "1_1") (pintype "passive"))
      (node (ref "U17") (pin "42") (pinfunction "PC7_42") (pintype "bidirectional"))
    )
    (net (code "50") (name "/D10") (class "Default")
      (node (ref "JP2") (pin "3") (pinfunction "3_3") (pintype "passive"))
      (node (ref "R3") (pin "2") (pinfunction "2_2") (pintype "passive"))
    )
    (net (code "51") (name "/D11") (class "Default")
      (node (ref "JP2") (pin "4") (pinfunction "4_4") (pintype "passive"))
      (node (ref "JP8") (pin "4") (pinfunction "4_4") (pintype "bidirectional"))
      (node (ref "R4") (pin "2") (pinfunction "2_2") (pintype "passive"))
    )
    (net (code "52") (name "/D12") (class "Default")
      (node (ref "JP2") (pin "5") (pinfunction "5_5") (pintype "passive"))
      (node (ref "JP8") (pin "1") (pinfunction "1_1") (pintype "bidirectional"))
      (node (ref "R5") (pin "2") (pinfunction "2_2") (pintype "passive"))
    )
    (net (code "53") (name "/D13") (class "Default")
      (node (ref "JP2") (pin "6") (pinfunction "6_6") (pintype "passive"))
      (node (ref "JP8") (pin "3") (pinfunction "3_3") (pintype "bidirectional"))
      (node (ref "R6") (pin "2") (pinfunction "2_2") (pintype "passive"))
    )
    (net (code "54") (name "/DTR") (class "Default")
      (node (ref "C4") (pin "1") (pinfunction "1_1") (pintype "passive"))
      (node (ref "R63") (pin "1") (pinfunction "1_1") (pintype "passive"))
    )
    (net (code "55") (name "/E") (class "Default")
      (node (ref "U$1") (pin "8") (pinfunction "8_8") (pintype "passive"))
      (node (ref "U17") (pin "35") (pinfunction "PC0_35") (pintype "bidirectional"))
    )
    (net (code "56") (name "/GND") (class "Default")
      (node (ref "C1") (pin "1") (pinfunction "1_1") (pintype "passive"))
      (node (ref "C2") (pin "1") (pinfunction "1_1") (pintype "passive"))
      (node (ref "C3") (pin "-") (pinfunction "-_-") (pintype "passive"))
      (node (ref "C5") (pin "2") (pinfunction "2_2") (pintype "passive"))
      (node (ref "C6") (pin "2") (pinfunction "2_2") (pintype "passive"))
      (node (ref "C7") (pin "2") (pinfunction "2_2") (pintype "passive"))
      (node (ref "C8") (pin "2") (pinfunction "2_2") (pintype "passive"))
      (node (ref "C9") (pin "2") (pinfunction "2_2") (pintype "passive"))
      (node (ref "D1") (pin "1") (pinfunction "A_1") (pintype "passive"))
      (node (ref "D10") (pin "1") (pinfunction "A_1") (pintype "passive"))
      (node (ref "D11") (pin "1") (pinfunction "A_1") (pintype "passive"))
      (node (ref "D12") (pin "1") (pinfunction "A_1") (pintype "passive"))
      (node (ref "D13") (pin "1") (pinfunction "A_1") (pintype "passive"))
      (node (ref "D14") (pin "1") (pinfunction "A_1") (pintype "passive"))
      (node (ref "D15") (pin "1") (pinfunction "A_1") (pintype "passive"))
      (node (ref "D16") (pin "1") (pinfunction "A_1") (pintype "passive"))
      (node (ref "D17") (pin "1") (pinfunction "A_1") (pintype "passive"))
      (node (ref "D18") (pin "1") (pinfunction "A_1") (pintype "passive"))
      (node (ref "D19") (pin "1") (pinfunction "A_1") (pintype "passive"))
      (node (ref "D2") (pin "1") (pinfunction "A_1") (pintype "passive"))
      (node (ref "D20") (pin "1") (pinfunction "A_1") (pintype "passive"))
      (node (ref "D21") (pin "1") (pinfunction "A_1") (pintype "passive"))
      (node (ref "D22") (pin "1") (pinfunction "A_1") (pintype "passive"))
      (node (ref "D23") (pin "1") (pinfunction "A_1") (pintype "passive"))
      (node (ref "D26") (pin "1") (pinfunction "A_1") (pintype "passive"))
      (node (ref "D27") (pin "1") (pinfunction "A_1") (pintype "passive"))
      (node (ref "D28") (pin "1") (pinfunction "A_1") (pintype "passive"))
      (node (ref "D29") (pin "1") (pinfunction "A_1") (pintype "passive"))
      (node (ref "D3") (pin "1") (pinfunction "A_1") (pintype "passive"))
      (node (ref "D32") (pin "1") (pinfunction "A_1") (pintype "passive"))
      (node (ref "D4") (pin "1") (pinfunction "A_1") (pintype "passive"))
      (node (ref "D5") (pin "1") (pinfunction "A_1") (pintype "passive"))
      (node (ref "D6") (pin "1") (pinfunction "A_1") (pintype "passive"))
      (node (ref "D7") (pin "1") (pinfunction "A_1") (pintype "passive"))
      (node (ref "D8") (pin "1") (pinfunction "A_1") (pintype "passive"))
      (node (ref "D9") (pin "1") (pinfunction "A_1") (pintype "passive"))
      (node (ref "IR") (pin "3") (pinfunction "3_3") (pintype "passive"))
      (node (ref "J1") (pin "GND") (pinfunction "GND_GND") (pintype "bidirectional"))
      (node (ref "J1") (pin "GNDBREAK") (pinfunction "GNDBREAK_GNDBREAK") (pintype "bidirectional"))
      (node (ref "JP10") (pin "5") (pinfunction "5_5") (pintype "bidirectional"))
      (node (ref "JP10") (pin "6") (pinfunction "6_6") (pintype "bidirectional"))
      (node (ref "JP11") (pin "5") (pinfunction "5_5") (pintype "bidirectional"))
      (node (ref "JP11") (pin "6") (pinfunction "6_6") (pintype "bidirectional"))
      (node (ref "JP2") (pin "7") (pinfunction "7_7") (pintype "passive"))
      (node (ref "JP4") (pin "4") (pinfunction "4_4") (pintype "passive"))
      (node (ref "JP4") (pin "5") (pinfunction "5_5") (pintype "passive"))
      (node (ref "JP7") (pin "1") (pinfunction "1_1") (pintype "passive"))
      (node (ref "JP7") (pin "2") (pinfunction "2_2") (pintype "passive"))
      (node (ref "JP7") (pin "3") (pinfunction "3_3") (pintype "passive"))
      (node (ref "JP7") (pin "4") (pinfunction "4_4") (pintype "passive"))
      (node (ref "JP8") (pin "6") (pinfunction "6_6") (pintype "bidirectional"))
      (node (ref "JP9") (pin "GND") (pinfunction "GND_GND") (pintype "bidirectional"))
      (node (ref "POWER") (pin "P$2") (pinfunction "P$2_P$2") (pintype "bidirectional"))
      (node (ref "R26") (pin "1") (pinfunction "1_1") (pintype "passive"))
      (node (ref "R28") (pin "1") (pinfunction "1_1") (pintype "passive"))
      (node (ref "R31") (pin "1") (pinfunction "1_1") (pintype "passive"))
      (node (ref "R34") (pin "1") (pinfunction "1_1") (pintype "passive"))
      (node (ref "R36") (pin "1") (pinfunction "1_1") (pintype "passive"))
      (node (ref "R41") (pin "1") (pinfunction "1_1") (pintype "passive"))
      (node (ref "R46") (pin "1") (pinfunction "1_1") (pintype "passive"))
      (node (ref "R51") (pin "1") (pinfunction "1_1") (pintype "passive"))
      (node (ref "R52") (pin "1") (pinfunction "1_1") (pintype "passive"))
      (node (ref "R53") (pin "1") (pinfunction "1_1") (pintype "passive"))
      (node (ref "R54") (pin "1") (pinfunction "1_1") (pintype "passive"))
      (node (ref "R60") (pin "1") (pinfunction "1_1") (pintype "passive"))
      (node (ref "R62") (pin "1") (pinfunction "1_1") (pintype "passive"))
      (node (ref "RESET") (pin "1") (pinfunction "1_1") (pintype "passive"))
      (node (ref "RESET") (pin "2") (pinfunction "2_2") (pintype "passive"))
      (node (ref "S2") (pin "1") (pinfunction "1_1") (pintype "passive"))
      (node (ref "S2") (pin "2") (pinfunction "2_2") (pintype "passive"))
      (node (ref "U$1") (pin "1") (pinfunction "1_1") (pintype "passive"))
      (node (ref "U$1") (pin "3") (pinfunction "3_3") (pintype "passive"))
      (node (ref "U$1") (pin "7") (pinfunction "7_7") (pintype "passive"))
      (node (ref "U$2") (pin "3") (pinfunction "E_3") (pintype "passive"))
      (node (ref "U$8") (pin "P$10") (pinfunction "GND2_P$10") (pintype "bidirectional"))
      (node (ref "U$8") (pin "P$12") (pinfunction "GND3_P$12") (pintype "bidirectional"))
      (node (ref "U$8") (pin "P$13") (pinfunction "NC3_P$13") (pintype "bidirectional"))
      (node (ref "U$8") (pin "P$5") (pinfunction "GND1_P$5") (pintype "bidirectional"))
      (node (ref "U$8") (pin "P$7") (pinfunction "SA0_P$7") (pintype "bidirectional"))
      (node (ref "U$8") (pin "P$8") (pinfunction "NC2_P$8") (pintype "bidirectional"))
      (node (ref "U1") (pin "18") (pinfunction "GND2_18") (pintype "power_in"))
      (node (ref "U1") (pin "21") (pinfunction "GND3_21") (pintype "power_in"))
      (node (ref "U1") (pin "25") (pinfunction "AGND_25") (pintype "power_in"))
      (node (ref "U1") (pin "26") (pinfunction "TEST_26") (pintype "input"))
      (node (ref "U1") (pin "7") (pinfunction "GND1_7") (pintype "power_in"))
      (node (ref "U10") (pin "GND") (pinfunction "GND_PPAD_GND") (pintype "bidirectional"))
      (node (ref "U10") (pin "P$5") (pinfunction "GND1_P$5") (pintype "bidirectional"))
      (node (ref "U10") (pin "P$6") (pinfunction "GND2_P$6") (pintype "bidirectional"))
      (node (ref "U11") (pin "4") (pinfunction "V-_4") (pintype "power_in"))
      (node (ref "U12") (pin "4") (pinfunction "V-_4") (pintype "power_in"))
      (node (ref "U16") (pin "4") (pinfunction "V-_4") (pintype "power_in"))
      (node (ref "U16") (pin "5") (pinfunction "+IN_5") (pintype "input"))
      (node (ref "U16") (pin "6") (pinfunction "-IN_6") (pintype "input"))
      (node (ref "U17") (pin "22") (pinfunction "GND1_22") (pintype "bidirectional"))
      (node (ref "U17") (pin "53") (pinfunction "GND2_53") (pintype "bidirectional"))
      (node (ref "U17") (pin "63") (pinfunction "GND3_63") (pintype "bidirectional"))
      (node (ref "U3") (pin "2") (pinfunction "GND_2") (pintype "input"))
      (node (ref "U4") (pin "13") (pinfunction "GND_13") (pintype "bidirectional"))
      (node (ref "U4") (pin "21") (pinfunction "GND1_21") (pintype "bidirectional"))
      (node (ref "U4") (pin "22") (pinfunction "GND2_22") (pintype "bidirectional"))
      (node (ref "U4") (pin "34") (pinfunction "PIO11_34") (pintype "bidirectional"))
      (node (ref "U7") (pin "P$2") (pinfunction "GND_P$2") (pintype "bidirectional"))
      (node (ref "U8") (pin "P$2") (pinfunction "GND_P$2") (pintype "bidirectional"))
      (node (ref "U9") (pin "GND") (pinfunction "GND_PPAD_GND") (pintype "bidirectional"))
      (node (ref "U9") (pin "P$5") (pinfunction "GND1_P$5") (pintype "bidirectional"))
      (node (ref "U9") (pin "P$6") (pinfunction "GND2_P$6") (pintype "bidirectional"))
    )
    (net (code "57") (name "/HIGH_5V_REG") (class "Default")
      (node (ref "U3") (pin "5") (pinfunction "OUT_5") (pintype "passive"))
      (node (ref "U6") (pin "S1") (pinfunction "S1_S1") (pintype "bidirectional"))
    )
    (net (code "58") (name "/IR") (class "Default")
      (node (ref "IR") (pin "1") (pinfunction "1_1") (pintype "passive"))
      (node (ref "U17") (pin "25") (pinfunction "PD0_25") (pintype "bidirectional"))
    )
    (net (code "59") (name "/LCD0") (class "Default")
      (node (ref "U$1") (pin "9") (pinfunction "9_9") (pintype "passive"))
      (node (ref "U17") (pin "51") (pinfunction "PA0_51") (pintype "bidirectional"))
    )
    (net (code "60") (name "/LCD1") (class "Default")
      (node (ref "U$1") (pin "10") (pinfunction "10_10") (pintype "passive"))
      (node (ref "U17") (pin "50") (pinfunction "PA1_50") (pintype "bidirectional"))
    )
    (net (code "61") (name "/LCD2") (class "Default")
      (node (ref "U$1") (pin "11") (pinfunction "11_11") (pintype "passive"))
      (node (ref "U17") (pin "49") (pinfunction "PA2_49") (pintype "bidirectional"))
    )
    (net (code "62") (name "/LCD3") (class "Default")
      (node (ref "U$1") (pin "12") (pinfunction "12_12") (pintype "passive"))
      (node (ref "U17") (pin "48") (pinfunction "PA3_48") (pintype "bidirectional"))
    )
    (net (code "63") (name "/LCD4") (class "Default")
      (node (ref "U$1") (pin "13") (pinfunction "13_13") (pintype "passive"))
      (node (ref "U17") (pin "47") (pinfunction "PA4_47") (pintype "bidirectional"))
    )
    (net (code "64") (name "/LCD5") (class "Default")
      (node (ref "U$1") (pin "14") (pinfunction "14_14") (pintype "passive"))
      (node (ref "U17") (pin "46") (pinfunction "PA5_46") (pintype "bidirectional"))
    )
    (net (code "65") (name "/LCD6") (class "Default")
      (node (ref "U$1") (pin "15") (pinfunction "15_15") (pintype "passive"))
      (node (ref "U17") (pin "45") (pinfunction "PA6_45") (pintype "bidirectional"))
    )
    (net (code "66") (name "/LCD7") (class "Default")
      (node (ref "U$1") (pin "16") (pinfunction "16_16") (pintype "passive"))
      (node (ref "U17") (pin "44") (pinfunction "PA7_44") (pintype "bidirectional"))
    )
    (net (code "67") (name "/LED0") (class "Default")
      (node (ref "D30") (pin "A") (pinfunction "A_A") (pintype "passive"))
      (node (ref "U17") (pin "33") (pinfunction "PG0_33") (pintype "bidirectional"))
    )
    (net (code "68") (name "/LED1") (class "Default")
      (node (ref "D31") (pin "A") (pinfunction "A_A") (pintype "passive"))
      (node (ref "U17") (pin "34") (pinfunction "PG1_34") (pintype "bidirectional"))
    )
    (net (code "69") (name "/M0_DIR0") (class "Default")
      (node (ref "U17") (pin "29") (pinfunction "PD4_29") (pintype "bidirectional"))
      (node (ref "U9") (pin "P$9") (pinfunction "IN1_P$9") (pintype "bidirectional"))
    )
    (net (code "70") (name "/M0_DIR1") (class "Default")
      (node (ref "U17") (pin "30") (pinfunction "PD5_30") (pintype "bidirectional"))
      (node (ref "U9") (pin "P$11") (pinfunction "IN2_P$11") (pintype "bidirectional"))
    )
    (net (code "71") (name "/M0_EN") (class "Default")
      (node (ref "U17") (pin "14") (pinfunction "PB4(OC0A)_14") (pintype "bidirectional"))
      (node (ref "U9") (pin "P$10") (pinfunction "EN1_P$10") (pintype "bidirectional"))
      (node (ref "U9") (pin "P$12") (pinfunction "EN2_P$12") (pintype "bidirectional"))
    )
    (net (code "72") (name "/M1_DIR0") (class "Default")
      (node (ref "U10") (pin "P$9") (pinfunction "IN1_P$9") (pintype "bidirectional"))
      (node (ref "U17") (pin "31") (pinfunction "PD6_31") (pintype "bidirectional"))
    )
    (net (code "73") (name "/M1_DIR1") (class "Default")
      (node (ref "U10") (pin "P$11") (pinfunction "IN2_P$11") (pintype "bidirectional"))
      (node (ref "U17") (pin "32") (pinfunction "PD7_32") (pintype "bidirectional"))
    )
    (net (code "74") (name "/M1_EN") (class "Default")
      (node (ref "U10") (pin "P$10") (pinfunction "EN1_P$10") (pintype "bidirectional"))
      (node (ref "U10") (pin "P$12") (pinfunction "EN2_P$12") (pintype "bidirectional"))
      (node (ref "U17") (pin "17") (pinfunction "PB7(OC2A)_17") (pintype "bidirectional"))
    )
    (net (code "75") (name "/MISO") (class "Default")
      (node (ref "D5") (pin "3") (pinfunction "C_3") (pintype "passive"))
      (node (ref "R5") (pin "1") (pinfunction "1_1") (pintype "passive"))
      (node (ref "U17") (pin "13") (pinfunction "PB3(MISO)_13") (pintype "bidirectional"))
    )
    (net (code "76") (name "/MOSI") (class "Default")
      (node (ref "D4") (pin "3") (pinfunction "C_3") (pintype "passive"))
      (node (ref "R4") (pin "1") (pinfunction "1_1") (pintype "passive"))
      (node (ref "U17") (pin "12") (pinfunction "PB2(MOSI)_12") (pintype "bidirectional"))
    )
    (net (code "77") (name "/N$33") (class "Default")
      (node (ref "F1") (pin "2") (pinfunction "2_2") (pintype "passive"))
      (node (ref "JP4") (pin "6") (pinfunction "6_6") (pintype "passive"))
      (node (ref "Q1") (pin "3") (pinfunction "D_3") (pintype "bidirectional"))
    )
    (net (code "78") (name "/PWR_SW") (class "Default")
      (node (ref "D33") (pin "1") (pinfunction "A1_1") (pintype "passive"))
      (node (ref "Q1") (pin "2") (pinfunction "S_2") (pintype "bidirectional"))
      (node (ref "Q2") (pin "2") (pinfunction "S_2") (pintype "bidirectional"))
      (node (ref "R44") (pin "1") (pinfunction "1_1") (pintype "passive"))
      (node (ref "U2") (pin "S2") (pinfunction "S2_S2") (pintype "bidirectional"))
    )
    (net (code "79") (name "/RESET") (class "Default")
      (node (ref "C4") (pin "2") (pinfunction "2_2") (pintype "passive"))
      (node (ref "R39") (pin "1") (pinfunction "1_1") (pintype "passive"))
      (node (ref "R40") (pin "2") (pinfunction "2_2") (pintype "passive"))
      (node (ref "R56") (pin "1") (pinfunction "1_1") (pintype "passive"))
      (node (ref "RESET") (pin "3") (pinfunction "3_3") (pintype "passive"))
      (node (ref "RESET") (pin "4") (pinfunction "4_4") (pintype "passive"))
      (node (ref "U17") (pin "20") (pinfunction "RESET/PG5_20") (pintype "bidirectional"))
    )
    (net (code "80") (name "/RS") (class "Default")
      (node (ref "U$1") (pin "6") (pinfunction "6_6") (pintype "passive"))
      (node (ref "U17") (pin "36") (pinfunction "PC1_36") (pintype "bidirectional"))
    )
    (net (code "81") (name "/RX") (class "Default")
      (node (ref "U1") (pin "1") (pinfunction "TXD_1") (pintype "output"))
      (node (ref "U17") (pin "28") (pinfunction "PD3_28") (pintype "bidirectional"))
    )
    (net (code "82") (name "/SCK") (class "Default")
      (node (ref "D6") (pin "3") (pinfunction "C_3") (pintype "passive"))
      (node (ref "R6") (pin "1") (pinfunction "1_1") (pintype "passive"))
      (node (ref "U17") (pin "11") (pinfunction "PB1(SCK)_11") (pintype "bidirectional"))
    )
    (net (code "83") (name "/SCL0") (class "Default")
      (node (ref "JP2") (pin "9") (pinfunction "9_9") (pintype "passive"))
      (node (ref "R7") (pin "2") (pinfunction "2_2") (pintype "passive"))
    )
    (net (code "84") (name "/SCL_IN") (class "Default")
      (node (ref "D7") (pin "3") (pinfunction "C_3") (pintype "passive"))
      (node (ref "R38") (pin "1") (pinfunction "1_1") (pintype "passive"))
      (node (ref "R7") (pin "1") (pinfunction "1_1") (pintype "passive"))
      (node (ref "U$8") (pin "P$4") (pinfunction "SCL_P$4") (pintype "bidirectional"))
      (node (ref "U17") (pin "6") (pinfunction "PE4(SCL)_6") (pintype "bidirectional"))
    )
    (net (code "85") (name "/SDA0") (class "Default")
      (node (ref "JP2") (pin "10") (pinfunction "10_10") (pintype "passive"))
      (node (ref "R8") (pin "2") (pinfunction "2_2") (pintype "passive"))
    )
    (net (code "86") (name "/SDA_IN") (class "Default")
      (node (ref "D8") (pin "3") (pinfunction "C_3") (pintype "passive"))
      (node (ref "R37") (pin "1") (pinfunction "1_1") (pintype "passive"))
      (node (ref "R8") (pin "1") (pinfunction "1_1") (pintype "passive"))
      (node (ref "U$8") (pin "P$6") (pinfunction "SDA_P$6") (pintype "bidirectional"))
      (node (ref "U17") (pin "7") (pinfunction "PE5(SDA)_7") (pintype "bidirectional"))
    )
    (net (code "87") (name "/SERVO0") (class "Default")
      (node (ref "JP3") (pin "1") (pinfunction "1_1") (pintype "passive"))
      (node (ref "R47") (pin "2") (pinfunction "2_2") (pintype "passive"))
    )
    (net (code "88") (name "/SERVO0_IN") (class "Default")
      (node (ref "D26") (pin "3") (pinfunction "C_3") (pintype "passive"))
      (node (ref "R47") (pin "1") (pinfunction "1_1") (pintype "passive"))
      (node (ref "U17") (pin "37") (pinfunction "PC2_37") (pintype "bidirectional"))
    )
    (net (code "89") (name "/SERVO1") (class "Default")
      (node (ref "JP3") (pin "2") (pinfunction "2_2") (pintype "passive"))
      (node (ref "R48") (pin "2") (pinfunction "2_2") (pintype "passive"))
    )
    (net (code "90") (name "/SERVO1_IN") (class "Default")
      (node (ref "D27") (pin "3") (pinfunction "C_3") (pintype "passive"))
      (node (ref "R48") (pin "1") (pinfunction "1_1") (pintype "passive"))
      (node (ref "U17") (pin "38") (pinfunction "PC3_38") (pintype "bidirectional"))
    )
    (net (code "91") (name "/SERVO2") (class "Default")
      (node (ref "JP3") (pin "3") (pinfunction "3_3") (pintype "passive"))
      (node (ref "R49") (pin "2") (pinfunction "2_2") (pintype "passive"))
    )
    (net (code "92") (name "/SERVO2_IN") (class "Default")
      (node (ref "D28") (pin "3") (pinfunction "C_3") (pintype "passive"))
      (node (ref "R49") (pin "1") (pinfunction "1_1") (pintype "passive"))
      (node (ref "U17") (pin "39") (pinfunction "PC4_39") (pintype "bidirectional"))
    )
    (net (code "93") (name "/SERVO3") (class "Default")
      (node (ref "JP3") (pin "4") (pinfunction "4_4") (pintype "passive"))
      (node (ref "R50") (pin "2") (pinfunction "2_2") (pintype "passive"))
    )
    (net (code "94") (name "/SERVO3_IN") (class "Default")
      (node (ref "D29") (pin "3") (pinfunction "C_3") (pintype "passive"))
      (node (ref "R50") (pin "1") (pinfunction "1_1") (pintype "passive"))
      (node (ref "U17") (pin "54") (pinfunction "PF7(ADC7)_54") (pintype "bidirectional"))
    )
    (net (code "95") (name "/SS") (class "Default")
      (node (ref "D3") (pin "3") (pinfunction "C_3") (pintype "passive"))
      (node (ref "R3") (pin "1") (pinfunction "1_1") (pintype "passive"))
      (node (ref "U17") (pin "10") (pinfunction "PB0(SS)_10") (pintype "bidirectional"))
    )
    (net (code "96") (name "/SW1") (class "Default")
      (node (ref "S2") (pin "3") (pinfunction "3_3") (pintype "passive"))
      (node (ref "S2") (pin "4") (pinfunction "4_4") (pintype "passive"))
      (node (ref "U17") (pin "9") (pinfunction "PE7_9") (pintype "bidirectional"))
    )
    (net (code "97") (name "/TX") (class "Default")
      (node (ref "U1") (pin "5") (pinfunction "RXD_5") (pintype "input"))
      (node (ref "U17") (pin "27") (pinfunction "PD2_27") (pintype "bidirectional"))
    )
    (net (code "98") (name "/USBGATE") (class "Default")
      (node (ref "R42") (pin "1") (pinfunction "1_1") (pintype "passive"))
      (node (ref "R60") (pin "2") (pinfunction "2_2") (pintype "passive"))
      (node (ref "U16") (pin "1") (pinfunction "OUT_1") (pintype "output"))
      (node (ref "U2") (pin "G1") (pinfunction "G1_G1") (pintype "bidirectional"))
      (node (ref "U2") (pin "G2") (pinfunction "G2_G2") (pintype "bidirectional"))
    )
    (net (code "99") (name "/USB_5V") (class "Default")
      (node (ref "D33") (pin "2") (pinfunction "A2_2") (pintype "passive"))
      (node (ref "F2") (pin "2") (pinfunction "2_2") (pintype "passive"))
      (node (ref "R54") (pin "2") (pinfunction "2_2") (pintype "passive"))
      (node (ref "R55") (pin "1") (pinfunction "1_1") (pintype "passive"))
      (node (ref "U1") (pin "20") (pinfunction "VCC_20") (pintype "power_in"))
      (node (ref "U1") (pin "4") (pinfunction "VCCIO_4") (pintype "power_in"))
      (node (ref "U16") (pin "8") (pinfunction "V+_8") (pintype "power_in"))
      (node (ref "U2") (pin "S1") (pinfunction "S1_S1") (pintype "bidirectional"))
    )
    (net (code "100") (name "/VIN") (class "Default")
      (node (ref "F1") (pin "1") (pinfunction "1_1") (pintype "passive"))
      (node (ref "J1") (pin "PWR") (pinfunction "PWR_PWR") (pintype "bidirectional"))
      (node (ref "R35") (pin "2") (pinfunction "2_2") (pintype "passive"))
    )
    (net (code "101") (name "/VIN_F") (class "Default")
      (node (ref "JP6") (pin "1") (pinfunction "1_1") (pintype "passive"))
      (node (ref "JP6") (pin "2") (pinfunction "2_2") (pintype "passive"))
      (node (ref "JP6") (pin "3") (pinfunction "3_3") (pintype "passive"))
      (node (ref "JP6") (pin "4") (pinfunction "4_4") (pintype "passive"))
      (node (ref "Q2") (pin "3") (pinfunction "D_3") (pintype "bidirectional"))
      (node (ref "R29") (pin "2") (pinfunction "2_2") (pintype "passive"))
      (node (ref "R32") (pin "2") (pinfunction "2_2") (pintype "passive"))
      (node (ref "R33") (pin "2") (pinfunction "2_2") (pintype "passive"))
      (node (ref "R45") (pin "2") (pinfunction "2_2") (pintype "passive"))
      (node (ref "U10") (pin "P$1") (pinfunction "VM1_P$1") (pintype "bidirectional"))
      (node (ref "U10") (pin "P$2") (pinfunction "VM2_P$2") (pintype "bidirectional"))
      (node (ref "U11") (pin "8") (pinfunction "V+_8") (pintype "power_in"))
      (node (ref "U12") (pin "8") (pinfunction "V+_8") (pintype "power_in"))
      (node (ref "U3") (pin "1") (pinfunction "IN_1") (pintype "input"))
      (node (ref "U3") (pin "3") (pinfunction "EN_3") (pintype "input"))
      (node (ref "U5") (pin "S1") (pinfunction "S1_S1") (pintype "bidirectional"))
      (node (ref "U9") (pin "P$1") (pinfunction "VM1_P$1") (pintype "bidirectional"))
      (node (ref "U9") (pin "P$2") (pinfunction "VM2_P$2") (pintype "bidirectional"))
    )
    (net (code "102") (name "Net-(D25-PadC)") (class "Default")
      (node (ref "D25") (pin "C") (pinfunction "C_C") (pintype "passive"))
      (node (ref "R41") (pin "2") (pinfunction "2_2") (pintype "passive"))
    )
    (net (code "103") (name "Net-(D30-PadC)") (class "Default")
      (node (ref "D30") (pin "C") (pinfunction "C_C") (pintype "passive"))
      (node (ref "R51") (pin "2") (pinfunction "2_2") (pintype "passive"))
    )
    (net (code "104") (name "Net-(D31-PadC)") (class "Default")
      (node (ref "D31") (pin "C") (pinfunction "C_C") (pintype "passive"))
      (node (ref "R52") (pin "2") (pinfunction "2_2") (pintype "passive"))
    )
    (net (code "105") (name "Net-(D33-CC)") (class "Default")
      (node (ref "D33") (pin "3") (pinfunction "CC_3") (pintype "passive"))
      (node (ref "R42") (pin "2") (pinfunction "2_2") (pintype "passive"))
    )
    (net (code "106") (name "Net-(D34-PadA)") (class "Default")
      (node (ref "D34") (pin "A") (pinfunction "A_A") (pintype "passive"))
      (node (ref "R57") (pin "2") (pinfunction "2_2") (pintype "passive"))
    )
    (net (code "107") (name "Net-(F2-Pad1)") (class "Default")
      (node (ref "F2") (pin "1") (pinfunction "1_1") (pintype "passive"))
      (node (ref "JP9") (pin "VBUS") (pinfunction "VBUS_VBUS") (pintype "bidirectional"))
    )
    (net (code "108") (name "Net-(JP4-Pad1)") (class "Default")
      (node (ref "JP4") (pin "1") (pinfunction "1_1") (pintype "passive"))
      (node (ref "R56") (pin "2") (pinfunction "2_2") (pintype "passive"))
    )
    (net (code "109") (name "Net-(JP8-Pad5)") (class "Default")
      (node (ref "JP8") (pin "5") (pinfunction "5_5") (pintype "bidirectional"))
      (node (ref "R39") (pin "2") (pinfunction "2_2") (pintype "passive"))
    )
    (net (code "110") (name "Net-(POWER-PadP$1)") (class "Default")
      (node (ref "POWER") (pin "P$1") (pinfunction "P$1_P$1") (pintype "bidirectional"))
      (node (ref "R43") (pin "2") (pinfunction "2_2") (pintype "passive"))
    )
    (net (code "111") (name "Net-(Q1-G)") (class "Default")
      (node (ref "Q1") (pin "1") (pinfunction "G_1") (pintype "bidirectional"))
      (node (ref "R34") (pin "2") (pinfunction "2_2") (pintype "passive"))
    )
    (net (code "112") (name "Net-(Q2-G)") (class "Default")
      (node (ref "Q2") (pin "1") (pinfunction "G_1") (pintype "bidirectional"))
      (node (ref "R43") (pin "1") (pinfunction "1_1") (pintype "passive"))
      (node (ref "R44") (pin "2") (pinfunction "2_2") (pintype "passive"))
    )
    (net (code "113") (name "Net-(Q3-G)") (class "Default")
      (node (ref "Q3") (pin "1") (pinfunction "G_1") (pintype "bidirectional"))
      (node (ref "R25") (pin "1") (pinfunction "1_1") (pintype "passive"))
      (node (ref "U12") (pin "7") (pinfunction "OUT_7") (pintype "output"))
    )
    (net (code "114") (name "Net-(Q4-G)") (class "Default")
      (node (ref "Q4") (pin "1") (pinfunction "G_1") (pintype "bidirectional"))
      (node (ref "R30") (pin "1") (pinfunction "1_1") (pintype "passive"))
      (node (ref "U12") (pin "1") (pinfunction "OUT_1") (pintype "output"))
    )
    (net (code "115") (name "Net-(R64-Pad2)") (class "Default")
      (node (ref "R64") (pin "2") (pinfunction "2_2") (pintype "passive"))
      (node (ref "U$1") (pin "2") (pinfunction "2_2") (pintype "passive"))
    )
    (net (code "116") (name "Net-(U$2-S)") (class "Default")
      (node (ref "U$1") (pin "5") (pinfunction "5_5") (pintype "passive"))
      (node (ref "U$2") (pin "2") (pinfunction "S_2") (pintype "passive"))
    )
    (net (code "117") (name "Net-(U$8-BYP)") (class "Default")
      (node (ref "C5") (pin "1") (pinfunction "1_1") (pintype "passive"))
      (node (ref "U$8") (pin "P$2") (pinfunction "BYP_P$2") (pintype "bidirectional"))
    )
    (net (code "118") (name "Net-(U1-DTR)") (class "Default")
      (node (ref "R63") (pin "2") (pinfunction "2_2") (pintype "passive"))
      (node (ref "U1") (pin "2") (pinfunction "DTR_2") (pintype "bidirectional"))
    )
    (net (code "119") (name "Net-(U1-RXLED)") (class "Default")
      (node (ref "D34") (pin "C") (pinfunction "C_C") (pintype "passive"))
      (node (ref "U1") (pin "22") (pinfunction "RXLED_22") (pintype "bidirectional"))
    )
    (net (code "120") (name "Net-(U1-USBDM)") (class "Default")
      (node (ref "JP9") (pin "D-") (pinfunction "D-_D-") (pintype "bidirectional"))
      (node (ref "U1") (pin "16") (pinfunction "USBDM_16") (pintype "bidirectional"))
    )
    (net (code "121") (name "Net-(U1-USBDP)") (class "Default")
      (node (ref "JP9") (pin "D+") (pinfunction "D+_D+") (pintype "bidirectional"))
      (node (ref "U1") (pin "15") (pinfunction "USBDP_15") (pintype "bidirectional"))
    )
    (net (code "122") (name "Net-(U2-D1-PadD1@)") (class "Default")
      (node (ref "U2") (pin "D1") (pinfunction "D1_D1") (pintype "bidirectional"))
      (node (ref "U2") (pin "D1@") (pinfunction "D1_D1@") (pintype "bidirectional"))
      (node (ref "U2") (pin "D2") (pinfunction "D2_D2") (pintype "bidirectional"))
      (node (ref "U2") (pin "D2@") (pinfunction "D2_D2@") (pintype "bidirectional"))
    )
    (net (code "123") (name "Net-(U4-RX)") (class "Default")
      (node (ref "R61") (pin "1") (pinfunction "1_1") (pintype "passive"))
      (node (ref "R62") (pin "2") (pinfunction "2_2") (pintype "passive"))
      (node (ref "U4") (pin "2") (pinfunction "RX_2") (pintype "bidirectional"))
    )
    (net (code "124") (name "Net-(U5-D1-PadD1@)") (class "Default")
      (node (ref "U5") (pin "D1") (pinfunction "D1_D1") (pintype "bidirectional"))
      (node (ref "U5") (pin "D1@") (pinfunction "D1_D1@") (pintype "bidirectional"))
      (node (ref "U5") (pin "D2") (pinfunction "D2_D2") (pintype "bidirectional"))
      (node (ref "U5") (pin "D2@") (pinfunction "D2_D2@") (pintype "bidirectional"))
    )
    (net (code "125") (name "Net-(U6-D1-PadD1@)") (class "Default")
      (node (ref "U6") (pin "D1") (pinfunction "D1_D1") (pintype "bidirectional"))
      (node (ref "U6") (pin "D1@") (pinfunction "D1_D1@") (pintype "bidirectional"))
      (node (ref "U6") (pin "D2") (pinfunction "D2_D2") (pintype "bidirectional"))
      (node (ref "U6") (pin "D2@") (pinfunction "D2_D2@") (pintype "bidirectional"))
    )
    (net (code "126") (name "Net-(U8-ILIM)") (class "Default")
      (node (ref "R53") (pin "2") (pinfunction "2_2") (pintype "passive"))
      (node (ref "U8") (pin "P$5") (pinfunction "ILIM_P$5") (pintype "bidirectional"))
    )
    (net (code "127") (name "Net-(U11A-+IN)") (class "Default")
      (node (ref "R28") (pin "2") (pinfunction "2_2") (pintype "passive"))
      (node (ref "R29") (pin "1") (pinfunction "1_1") (pintype "passive"))
      (node (ref "R58") (pin "2") (pinfunction "2_2") (pintype "passive"))
      (node (ref "U11") (pin "3") (pinfunction "+IN_3") (pintype "input"))
    )
    (net (code "128") (name "Net-(U12A-+IN)") (class "Default")
      (node (ref "R27") (pin "1") (pinfunction "1_1") (pintype "passive"))
      (node (ref "R31") (pin "2") (pinfunction "2_2") (pintype "passive"))
      (node (ref "U12") (pin "3") (pinfunction "+IN_3") (pintype "input"))
    )
    (net (code "129") (name "Net-(U12B-+IN)") (class "Default")
      (node (ref "R24") (pin "1") (pinfunction "1_1") (pintype "passive"))
      (node (ref "R26") (pin "2") (pinfunction "2_2") (pintype "passive"))
      (node (ref "U12") (pin "5") (pinfunction "+IN_5") (pintype "input"))
    )
    (net (code "130") (name "Net-(U16A-+IN)") (class "Default")
      (node (ref "R35") (pin "1") (pinfunction "1_1") (pintype "passive"))
      (node (ref "R36") (pin "2") (pinfunction "2_2") (pintype "passive"))
      (node (ref "U16") (pin "3") (pinfunction "+IN_3") (pintype "input"))
    )
    (net (code "131") (name "Net-(U17-PF6(ADC6))") (class "Default")
      (node (ref "R45") (pin "1") (pinfunction "1_1") (pintype "passive"))
      (node (ref "R46") (pin "2") (pinfunction "2_2") (pintype "passive"))
      (node (ref "U17") (pin "55") (pinfunction "PF6(ADC6)_55") (pintype "bidirectional"))
    )
    (net (code "132") (name "Net-(U17-PG2)") (class "Default")
      (node (ref "R55") (pin "2") (pinfunction "2_2") (pintype "passive"))
      (node (ref "U17") (pin "43") (pinfunction "PG2_43") (pintype "bidirectional"))
    )
    (net (code "133") (name "Net-(U17-XTAL1)") (class "Default")
      (node (ref "C1") (pin "2") (pinfunction "2_2") (pintype "passive"))
      (node (ref "U17") (pin "24") (pinfunction "XTAL1_24") (pintype "bidirectional"))
      (node (ref "Y1") (pin "P$1") (pinfunction "1_P$1") (pintype "passive"))
    )
    (net (code "134") (name "Net-(U17-XTAL2)") (class "Default")
      (node (ref "C2") (pin "2") (pinfunction "2_2") (pintype "passive"))
      (node (ref "U17") (pin "23") (pinfunction "XTAL2_23") (pintype "bidirectional"))
      (node (ref "Y1") (pin "P$2") (pinfunction "2_P$2") (pintype "passive"))
    )
    (net (code "135") (name "unconnected-(U$8-INT2-PadP$9)") (class "Default")
      (node (ref "U$8") (pin "P$9") (pinfunction "INT2_P$9") (pintype "bidirectional"))
    )
    (net (code "136") (name "unconnected-(U$8-NC1-PadP$3)") (class "Default")
      (node (ref "U$8") (pin "P$3") (pinfunction "NC1_P$3") (pintype "bidirectional"))
    )
    (net (code "137") (name "unconnected-(U1-3V3OUT-Pad17)") (class "Default")
      (node (ref "U1") (pin "17") (pinfunction "3V3OUT_17") (pintype "output"))
    )
    (net (code "138") (name "unconnected-(U1-CTS-Pad11)") (class "Default")
      (node (ref "U1") (pin "11") (pinfunction "CTS_11") (pintype "bidirectional"))
    )
    (net (code "139") (name "unconnected-(U1-RTS-Pad3)") (class "Default")
      (node (ref "U1") (pin "3") (pinfunction "RTS_3") (pintype "bidirectional"))
    )
    (net (code "140") (name "unconnected-(U1-TXLED-Pad23)") (class "Default")
      (node (ref "U1") (pin "23") (pinfunction "TXLED_23") (pintype "bidirectional"))
    )
    (net (code "141") (name "unconnected-(U3-BP-Pad4)") (class "Default")
      (node (ref "U3") (pin "4") (pinfunction "BP_4") (pintype "input"))
    )
    (net (code "142") (name "unconnected-(U4-AIO0-Pad9)") (class "Default")
      (node (ref "U4") (pin "9") (pinfunction "AIO0_9") (pintype "bidirectional"))
    )
    (net (code "143") (name "unconnected-(U4-AIO1-Pad10)") (class "Default")
      (node (ref "U4") (pin "10") (pinfunction "AIO1_10") (pintype "bidirectional"))
    )
    (net (code "144") (name "unconnected-(U4-CLK-Pad19)") (class "Default")
      (node (ref "U4") (pin "19") (pinfunction "CLK_19") (pintype "bidirectional"))
    )
    (net (code "145") (name "unconnected-(U4-CSB-Pad16)") (class "Default")
      (node (ref "U4") (pin "16") (pinfunction "CSB_16") (pintype "bidirectional"))
    )
    (net (code "146") (name "unconnected-(U4-CTS-Pad3)") (class "Default")
      (node (ref "U4") (pin "3") (pinfunction "CTS_3") (pintype "bidirectional"))
    )
    (net (code "147") (name "unconnected-(U4-MISO-Pad18)") (class "Default")
      (node (ref "U4") (pin "18") (pinfunction "MISO_18") (pintype "bidirectional"))
    )
    (net (code "148") (name "unconnected-(U4-MOSI-Pad17)") (class "Default")
      (node (ref "U4") (pin "17") (pinfunction "MOSI_17") (pintype "bidirectional"))
    )
    (net (code "149") (name "unconnected-(U4-NC-Pad14)") (class "Default")
      (node (ref "U4") (pin "14") (pinfunction "NC_14") (pintype "bidirectional"))
    )
    (net (code "150") (name "unconnected-(U4-PCM_CLK-Pad5)") (class "Default")
      (node (ref "U4") (pin "5") (pinfunction "PCM_CLK_5") (pintype "bidirectional"))
    )
    (net (code "151") (name "unconnected-(U4-PCM_IN-Pad7)") (class "Default")
      (node (ref "U4") (pin "7") (pinfunction "PCM_IN_7") (pintype "bidirectional"))
    )
    (net (code "152") (name "unconnected-(U4-PCM_OUT-Pad6)") (class "Default")
      (node (ref "U4") (pin "6") (pinfunction "PCM_OUT_6") (pintype "bidirectional"))
    )
    (net (code "153") (name "unconnected-(U4-PCN_SYNC-Pad8)") (class "Default")
      (node (ref "U4") (pin "8") (pinfunction "PCN_SYNC_8") (pintype "bidirectional"))
    )
    (net (code "154") (name "unconnected-(U4-PIO0-Pad23)") (class "Default")
      (node (ref "U4") (pin "23") (pinfunction "PIO0_23") (pintype "bidirectional"))
    )
    (net (code "155") (name "unconnected-(U4-PIO1-Pad24)") (class "Default")
      (node (ref "U4") (pin "24") (pinfunction "PIO1_24") (pintype "bidirectional"))
    )
    (net (code "156") (name "unconnected-(U4-PIO2-Pad25)") (class "Default")
      (node (ref "U4") (pin "25") (pinfunction "PIO2_25") (pintype "bidirectional"))
    )
    (net (code "157") (name "unconnected-(U4-PIO3-Pad26)") (class "Default")
      (node (ref "U4") (pin "26") (pinfunction "PIO3_26") (pintype "bidirectional"))
    )
    (net (code "158") (name "unconnected-(U4-PIO4-Pad27)") (class "Default")
      (node (ref "U4") (pin "27") (pinfunction "PIO4_27") (pintype "bidirectional"))
    )
    (net (code "159") (name "unconnected-(U4-PIO5-Pad28)") (class "Default")
      (node (ref "U4") (pin "28") (pinfunction "PIO5_28") (pintype "bidirectional"))
    )
    (net (code "160") (name "unconnected-(U4-PIO6-Pad29)") (class "Default")
      (node (ref "U4") (pin "29") (pinfunction "PIO6_29") (pintype "bidirectional"))
    )
    (net (code "161") (name "unconnected-(U4-PIO7-Pad30)") (class "Default")
      (node (ref "U4") (pin "30") (pinfunction "PIO7_30") (pintype "bidirectional"))
    )
    (net (code "162") (name "unconnected-(U4-PIO8-Pad31)") (class "Default")
      (node (ref "U4") (pin "31") (pinfunction "PIO8_31") (pintype "bidirectional"))
    )
    (net (code "163") (name "unconnected-(U4-PIO9-Pad32)") (class "Default")
      (node (ref "U4") (pin "32") (pinfunction "PIO9_32") (pintype "bidirectional"))
    )
    (net (code "164") (name "unconnected-(U4-PIO10-Pad33)") (class "Default")
      (node (ref "U4") (pin "33") (pinfunction "PIO10_33") (pintype "bidirectional"))
    )
    (net (code "165") (name "unconnected-(U4-RST-Pad11)") (class "Default")
      (node (ref "U4") (pin "11") (pinfunction "RST_11") (pintype "bidirectional"))
    )
    (net (code "166") (name "unconnected-(U4-RTS-Pad4)") (class "Default")
      (node (ref "U4") (pin "4") (pinfunction "RTS_4") (pintype "bidirectional"))
    )
    (net (code "167") (name "unconnected-(U4-VBUSD+-Pad20)") (class "Default")
      (node (ref "U4") (pin "20") (pinfunction "VBUSD+_20") (pintype "bidirectional"))
    )
    (net (code "168") (name "unconnected-(U4-VBUSD--Pad15)") (class "Default")
      (node (ref "U4") (pin "15") (pinfunction "VBUSD-_15") (pintype "bidirectional"))
    )
    (net (code "169") (name "unconnected-(U7-NC-PadP$5)") (class "Default")
      (node (ref "U7") (pin "P$5") (pinfunction "NC_P$5") (pintype "bidirectional"))
    )
    (net (code "170") (name "unconnected-(U8-FAULT-PadP$4)") (class "Default")
      (node (ref "U8") (pin "P$4") (pinfunction "FAULT_P$4") (pintype "bidirectional"))
    )
    (net (code "171") (name "unconnected-(U16B-OUT-Pad7)") (class "Default")
      (node (ref "U16") (pin "7") (pinfunction "OUT_7") (pintype "output"))
    )
    (net (code "172") (name "unconnected-(U17-NC-Pad1)") (class "Default")
      (node (ref "U17") (pin "1") (pinfunction "NC_1") (pintype "bidirectional"))
    )
  )
)
